# Extension_CN.net
KiCad netlist of a schematic drawn in Altium Designer
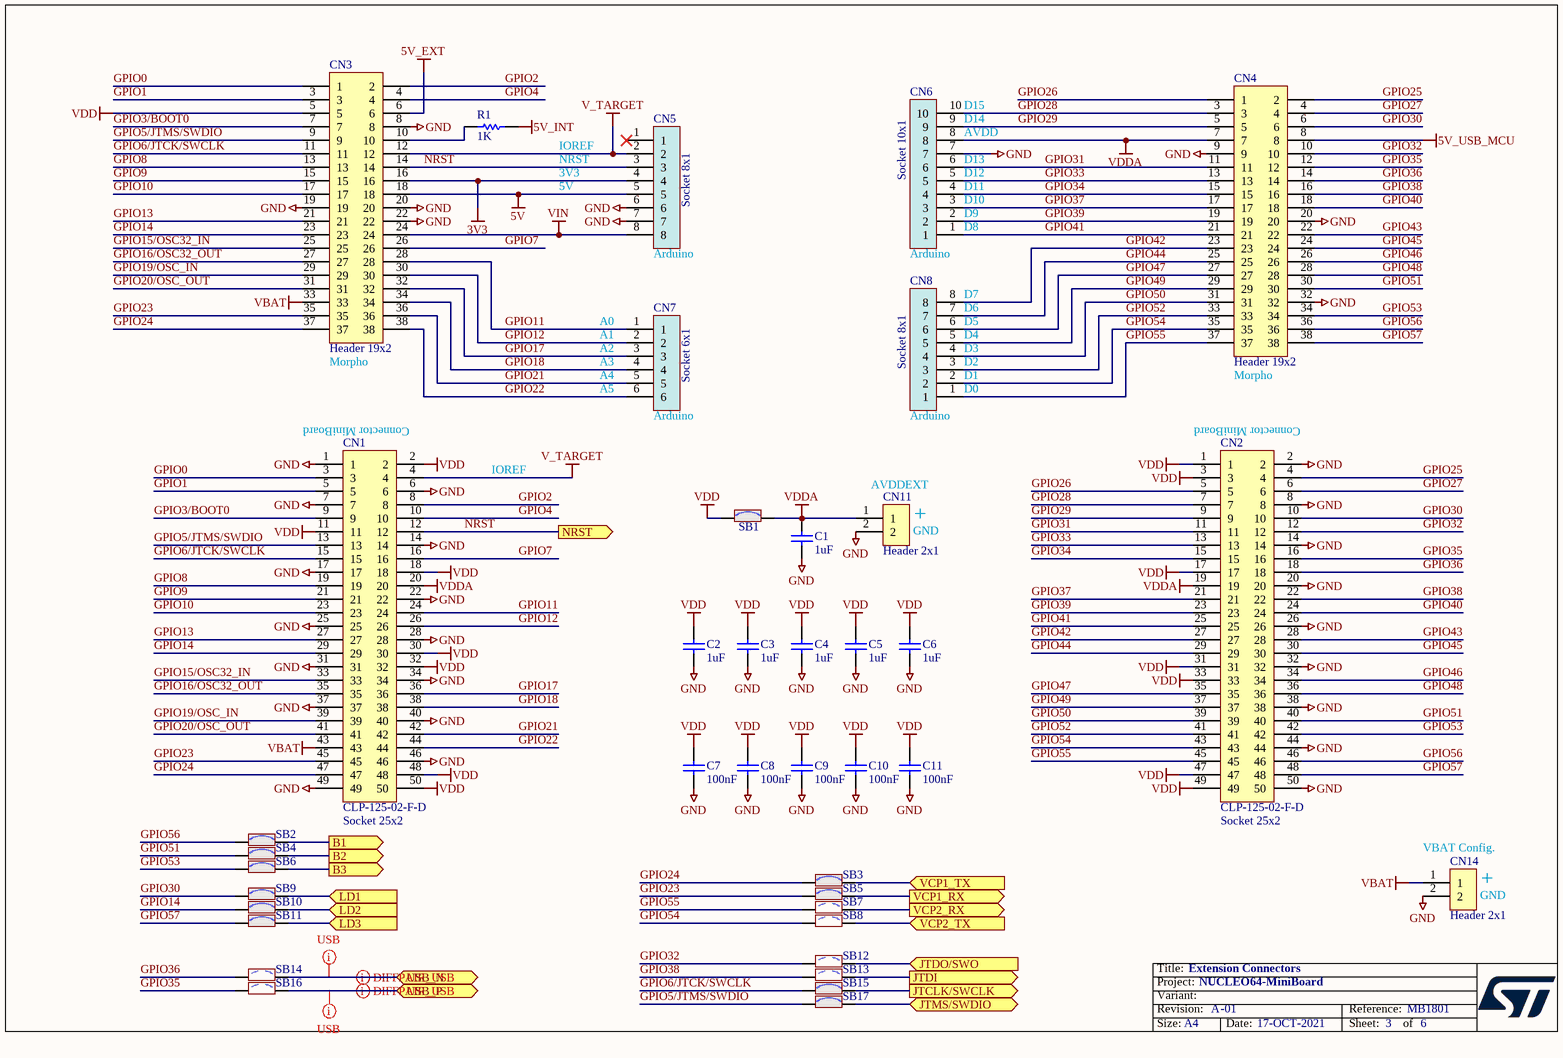
[diagram p0: Extension_CN.SchDoc]

(export (version "E")
  (design (tool "Eeschema 10.0.6"))
  (components
    (comp (ref "C1")
      (value "1uF")
      (footprint "C0805_H0P85")
      (description "Capacitor, MLCC, 1uF, 16V, X5R, +/-10%, 0805, T=0.85mm")
      (fields
        (field (name "INTERNAL_PART_NUMBER") "MCD-01550")
        (field (name "MANUFACTURER_PART_NUMBER") "CC0805KRX5R7BB105")
      )
      (libsource (lib "MCD_PARTS_database") (part "Capacitor"))
    )
    (comp (ref "C2")
      (value "1uF")
      (footprint "C0805_H0P85")
      (description "Capacitor, MLCC, 1uF, 16V, X5R, +/-10%, 0805, T=0.85mm")
      (fields
        (field (name "INTERNAL_PART_NUMBER") "MCD-01550")
        (field (name "MANUFACTURER_PART_NUMBER") "CC0805KRX5R7BB105")
      )
      (libsource (lib "MCD_PARTS_database") (part "Capacitor"))
    )
    (comp (ref "C3")
      (value "1uF")
      (footprint "C0805_H0P85")
      (description "Capacitor, MLCC, 1uF, 16V, X5R, +/-10%, 0805, T=0.85mm")
      (fields
        (field (name "INTERNAL_PART_NUMBER") "MCD-01550")
        (field (name "MANUFACTURER_PART_NUMBER") "CC0805KRX5R7BB105")
      )
      (libsource (lib "MCD_PARTS_database") (part "Capacitor"))
    )
    (comp (ref "C4")
      (value "1uF")
      (footprint "C0805_H0P85")
      (description "Capacitor, MLCC, 1uF, 16V, X5R, +/-10%, 0805, T=0.85mm")
      (fields
        (field (name "INTERNAL_PART_NUMBER") "MCD-01550")
        (field (name "MANUFACTURER_PART_NUMBER") "CC0805KRX5R7BB105")
      )
      (libsource (lib "MCD_PARTS_database") (part "Capacitor"))
    )
    (comp (ref "C5")
      (value "1uF")
      (footprint "C0805_H0P85")
      (description "Capacitor, MLCC, 1uF, 16V, X5R, +/-10%, 0805, T=0.85mm")
      (fields
        (field (name "INTERNAL_PART_NUMBER") "MCD-01550")
        (field (name "MANUFACTURER_PART_NUMBER") "CC0805KRX5R7BB105")
      )
      (libsource (lib "MCD_PARTS_database") (part "Capacitor"))
    )
    (comp (ref "C6")
      (value "1uF")
      (footprint "C0805_H0P85")
      (description "Capacitor, MLCC, 1uF, 16V, X5R, +/-10%, 0805, T=0.85mm")
      (fields
        (field (name "INTERNAL_PART_NUMBER") "MCD-01550")
        (field (name "MANUFACTURER_PART_NUMBER") "CC0805KRX5R7BB105")
      )
      (libsource (lib "MCD_PARTS_database") (part "Capacitor"))
    )
    (comp (ref "C7")
      (value "100nF")
      (footprint "C0402")
      (description "Capacitor, MLCC, 100nF, 25V, X7R, +/-10%, 0402, T=0.5mm")
      (fields (field (name "INTERNAL_PART_NUMBER") "MCD-02355") (field (name "MANUFACTURER") "WALSIN"))
      (libsource (lib "MCD_PARTS_database") (part "Capacitor"))
    )
    (comp (ref "C8")
      (value "100nF")
      (footprint "C0402")
      (description "Capacitor, MLCC, 100nF, 25V, X7R, +/-10%, 0402, T=0.5mm")
      (fields (field (name "INTERNAL_PART_NUMBER") "MCD-02355") (field (name "MANUFACTURER") "WALSIN"))
      (libsource (lib "MCD_PARTS_database") (part "Capacitor"))
    )
    (comp (ref "C9")
      (value "100nF")
      (footprint "C0402")
      (description "Capacitor, MLCC, 100nF, 25V, X7R, +/-10%, 0402, T=0.5mm")
      (fields (field (name "INTERNAL_PART_NUMBER") "MCD-02355") (field (name "MANUFACTURER") "WALSIN"))
      (libsource (lib "MCD_PARTS_database") (part "Capacitor"))
    )
    (comp (ref "C10")
      (value "100nF")
      (footprint "C0402")
      (description "Capacitor, MLCC, 100nF, 25V, X7R, +/-10%, 0402, T=0.5mm")
      (fields (field (name "INTERNAL_PART_NUMBER") "MCD-02355") (field (name "MANUFACTURER") "WALSIN"))
      (libsource (lib "MCD_PARTS_database") (part "Capacitor"))
    )
    (comp (ref "C11")
      (value "100nF")
      (footprint "C0402")
      (description "Capacitor, MLCC, 100nF, 25V, X7R, +/-10%, 0402, T=0.5mm")
      (fields (field (name "INTERNAL_PART_NUMBER") "MCD-02355") (field (name "MANUFACTURER") "WALSIN"))
      (libsource (lib "MCD_PARTS_database") (part "Capacitor"))
    )
    (comp (ref "CN1")
      (value "CLP-125-02-F-D")
      (footprint "CON_SAMTEC_CLP-125-02-F-D")
      (description "Socket, 25x2, 1.27mm, VR, SMD, T=2.29mm")
      (fields
        (field (name "INTERNAL_PART_NUMBER") "MCD-02705")
        (field (name "ALTIUM_VALUE") "Socket 25x2")
        (field (name "MANUFACTURER") "SAMTEC")
      )
      (libsource (lib "MCD_PARTS_database") (part "CLP-125-02-F-D"))
    )
    (comp (ref "CN2")
      (value "CLP-125-02-F-D")
      (footprint "CON_SAMTEC_CLP-125-02-F-D")
      (description "Socket, 25x2, 1.27mm, VR, SMD, T=2.29mm")
      (fields
        (field (name "INTERNAL_PART_NUMBER") "MCD-02705")
        (field (name "ALTIUM_VALUE") "Socket 25x2")
        (field (name "MANUFACTURER") "SAMTEC")
      )
      (libsource (lib "MCD_PARTS_database") (part "CLP-125-02-F-D"))
    )
    (comp (ref "CN3")
      (value "Header 19x2")
      (footprint "CON_SAMTEC_TSW-119-09-X-D")
      (description "Header, 19x2, 2.54mm, VR, TH, T=5.84mm/10.16mm")
      (fields (field (name "INTERNAL_PART_NUMBER") "MCD-00213") (field (name "MANUFACTURER") "SAMTEC"))
      (libsource (lib "MCD_PARTS_database") (part "Header 19x2"))
    )
    (comp (ref "CN4")
      (value "Header 19x2")
      (footprint "CON_SAMTEC_TSW-119-09-X-D")
      (description "Header, 19x2, 2.54mm, VR, TH, T=5.84mm/10.16mm")
      (fields (field (name "INTERNAL_PART_NUMBER") "MCD-00213") (field (name "MANUFACTURER") "SAMTEC"))
      (libsource (lib "MCD_PARTS_database") (part "Header 19x2"))
    )
    (comp (ref "CN5")
      (value "Socket 8x1")
      (footprint "CON_SAMTEC_SSW-108-01-X-S")
      (description "Socket, 8x1, 2.54mm, VR, TH, T=8.51/2.64mm")
      (fields (field (name "INTERNAL_PART_NUMBER") "MCD-01743") (field (name "MANUFACTURER") "SAMTEC"))
      (libsource (lib "") (part "Socket 8x1_1"))
    )
    (comp (ref "CN6")
      (value "Socket 10x1")
      (footprint "CON_SAMTEC_SSW-110-01-X-S")
      (description "Socket, 10x1, 2.54mm, VR, TH, T=8.51/2.64mm")
      (fields (field (name "INTERNAL_PART_NUMBER") "MCD-02080") (field (name "MANUFACTURER") "SAMTEC"))
      (libsource (lib "MCD_PARTS_database") (part "Socket 10x1"))
    )
    (comp (ref "CN7")
      (value "Socket 6x1")
      (footprint "CON_SAMTEC_SSW-106-01-X-S")
      (description "Socket, 6x1, 2.54mm, VR, TH, T=8.51/2.64mm")
      (fields (field (name "INTERNAL_PART_NUMBER") "MCD-02079") (field (name "MANUFACTURER") "SAMTEC"))
      (libsource (lib "MCD_PARTS_database") (part "Socket 6x1"))
    )
    (comp (ref "CN8")
      (value "Socket 8x1")
      (footprint "CON_SAMTEC_SSW-108-01-X-S")
      (description "Socket, 8x1, 2.54mm, VR, TH, T=8.51/2.64mm")
      (fields (field (name "INTERNAL_PART_NUMBER") "MCD-01743") (field (name "MANUFACTURER") "SAMTEC"))
      (libsource (lib "MCD_PARTS_database") (part "Socket 8x1"))
    )
    (comp (ref "CN11")
      (value "Header 2x1")
      (footprint "CON_SAMTEC_TSW-102-07-G-S")
      (description "Header, 2x1, 2.54mm, VR, TH, T=5.84mm/2.54mm")
      (fields (field (name "INTERNAL_PART_NUMBER") "MCD-00032") (field (name "MANUFACTURER") "SAMTEC"))
      (libsource (lib "MCD_PARTS_database") (part "Header 2x1"))
    )
    (comp (ref "CN14")
      (value "Header 2x1")
      (footprint "CON_SAMTEC_TSW-102-07-G-S")
      (description "Header, 2x1, 2.54mm, VR, TH, T=5.84mm/2.54mm")
      (fields (field (name "INTERNAL_PART_NUMBER") "MCD-00032") (field (name "MANUFACTURER") "SAMTEC"))
      (libsource (lib "MCD_PARTS_database") (part "Header 2x1"))
    )
    (comp (ref "R1")
      (value "1K")
      (footprint "R0402")
      (description "Resistor, 1K, 0402, +/-1%,1/16W")
      (fields (field (name "INTERNAL_PART_NUMBER") "MCD-00061") (field (name "MANUFACTURER") "YAGEO"))
      (libsource (lib "MCD_PARTS_database") (part "Resistor"))
    )
    (comp (ref "SB1")
      (value "SB_ON")
      (footprint "SOLDER-BRIDGE_R0402-0R")
      (description "Solder Bridge 0402 ON")
      (fields (field (name "INTERNAL_PART_NUMBER") "MCD-01618") (field (name "MANUFACTURER") "YAGEO"))
      (libsource (lib "MCD_PARTS_database") (part "SB_ON"))
    )
    (comp (ref "SB2")
      (value "SB_ON")
      (footprint "SOLDER-BRIDGE_R0402-0R")
      (description "Solder Bridge 0402 ON")
      (fields (field (name "INTERNAL_PART_NUMBER") "MCD-01618") (field (name "MANUFACTURER") "YAGEO"))
      (libsource (lib "MCD_PARTS_database") (part "SB_ON"))
    )
    (comp (ref "SB3")
      (value "SB_ON")
      (footprint "SOLDER-BRIDGE_R0402-0R")
      (description "Solder Bridge 0402 ON")
      (fields (field (name "INTERNAL_PART_NUMBER") "MCD-01618") (field (name "MANUFACTURER") "YAGEO"))
      (libsource (lib "MCD_PARTS_database") (part "SB_ON"))
    )
    (comp (ref "SB4")
      (value "SB_ON")
      (footprint "SOLDER-BRIDGE_R0402-0R")
      (description "Solder Bridge 0402 ON")
      (fields (field (name "INTERNAL_PART_NUMBER") "MCD-01618") (field (name "MANUFACTURER") "YAGEO"))
      (libsource (lib "MCD_PARTS_database") (part "SB_ON"))
    )
    (comp (ref "SB5")
      (value "SB_ON")
      (footprint "SOLDER-BRIDGE_R0402-0R")
      (description "Solder Bridge 0402 ON")
      (fields (field (name "INTERNAL_PART_NUMBER") "MCD-01618") (field (name "MANUFACTURER") "YAGEO"))
      (libsource (lib "MCD_PARTS_database") (part "SB_ON"))
    )
    (comp (ref "SB6")
      (value "SB_ON")
      (footprint "SOLDER-BRIDGE_R0402-0R")
      (description "Solder Bridge 0402 ON")
      (fields (field (name "INTERNAL_PART_NUMBER") "MCD-01618") (field (name "MANUFACTURER") "YAGEO"))
      (libsource (lib "MCD_PARTS_database") (part "SB_ON"))
    )
    (comp (ref "SB7")
      (value "SB_OFF")
      (footprint "SOLDER-BRIDGE_R0402-0R")
      (description "Solder Bridge 0402 OFF")
      (fields (field (name "INTERNAL_PART_NUMBER") "MCD-02162") (field (name "MANUFACTURER") "YAGEO"))
      (libsource (lib "MCD_PARTS_database") (part "SB_OFF"))
    )
    (comp (ref "SB8")
      (value "SB_OFF")
      (footprint "SOLDER-BRIDGE_R0402-0R")
      (description "Solder Bridge 0402 OFF")
      (fields (field (name "INTERNAL_PART_NUMBER") "MCD-02162") (field (name "MANUFACTURER") "YAGEO"))
      (libsource (lib "MCD_PARTS_database") (part "SB_OFF"))
    )
    (comp (ref "SB9")
      (value "SB_ON")
      (footprint "SOLDER-BRIDGE_R0402-0R")
      (description "Solder Bridge 0402 ON")
      (fields (field (name "INTERNAL_PART_NUMBER") "MCD-01618") (field (name "MANUFACTURER") "YAGEO"))
      (libsource (lib "MCD_PARTS_database") (part "SB_ON"))
    )
    (comp (ref "SB10")
      (value "SB_ON")
      (footprint "SOLDER-BRIDGE_R0402-0R")
      (description "Solder Bridge 0402 ON")
      (fields (field (name "INTERNAL_PART_NUMBER") "MCD-01618") (field (name "MANUFACTURER") "YAGEO"))
      (libsource (lib "MCD_PARTS_database") (part "SB_ON"))
    )
    (comp (ref "SB11")
      (value "SB_ON")
      (footprint "SOLDER-BRIDGE_R0402-0R")
      (description "Solder Bridge 0402 ON")
      (fields (field (name "INTERNAL_PART_NUMBER") "MCD-01618") (field (name "MANUFACTURER") "YAGEO"))
      (libsource (lib "MCD_PARTS_database") (part "SB_ON"))
    )
    (comp (ref "SB12")
      (value "SB_OFF")
      (footprint "SOLDER-BRIDGE_R0402-0R")
      (description "Solder Bridge 0402 OFF")
      (fields (field (name "INTERNAL_PART_NUMBER") "MCD-02162") (field (name "MANUFACTURER") "YAGEO"))
      (libsource (lib "MCD_PARTS_database") (part "SB_OFF"))
    )
    (comp (ref "SB13")
      (value "SB_OFF")
      (footprint "SOLDER-BRIDGE_R0402-0R")
      (description "Solder Bridge 0402 OFF")
      (fields (field (name "INTERNAL_PART_NUMBER") "MCD-02162") (field (name "MANUFACTURER") "YAGEO"))
      (libsource (lib "MCD_PARTS_database") (part "SB_OFF"))
    )
    (comp (ref "SB14")
      (value "SB_OFF")
      (footprint "SOLDER-BRIDGE_R0402-0R")
      (description "Solder Bridge 0402 OFF")
      (fields (field (name "INTERNAL_PART_NUMBER") "MCD-02162") (field (name "MANUFACTURER") "YAGEO"))
      (libsource (lib "MCD_PARTS_database") (part "SB_OFF"))
    )
    (comp (ref "SB15")
      (value "SB_ON")
      (footprint "SOLDER-BRIDGE_R0402-0R")
      (description "Solder Bridge 0402 ON")
      (fields (field (name "INTERNAL_PART_NUMBER") "MCD-01618") (field (name "MANUFACTURER") "YAGEO"))
      (libsource (lib "MCD_PARTS_database") (part "SB_ON"))
    )
    (comp (ref "SB16")
      (value "SB_OFF")
      (footprint "SOLDER-BRIDGE_R0402-0R")
      (description "Solder Bridge 0402 OFF")
      (fields (field (name "INTERNAL_PART_NUMBER") "MCD-02162") (field (name "MANUFACTURER") "YAGEO"))
      (libsource (lib "MCD_PARTS_database") (part "SB_OFF"))
    )
    (comp (ref "SB17")
      (value "SB_ON")
      (footprint "SOLDER-BRIDGE_R0402-0R")
      (description "Solder Bridge 0402 ON")
      (fields (field (name "INTERNAL_PART_NUMBER") "MCD-01618") (field (name "MANUFACTURER") "YAGEO"))
      (libsource (lib "MCD_PARTS_database") (part "SB_ON"))
    )
  )
  (nets
    (net (code "1") (name "/B1") (class "Default")
      (node (ref "SB2") (pin "2") (pinfunction "2_2") (pintype "passive"))
    )
    (net (code "2") (name "/B2") (class "Default")
      (node (ref "SB4") (pin "2") (pinfunction "2_2") (pintype "passive"))
    )
    (net (code "3") (name "/B3") (class "Default")
      (node (ref "SB6") (pin "2") (pinfunction "2_2") (pintype "passive"))
    )
    (net (code "4") (name "/GPIO0") (class "Default")
      (node (ref "CN1") (pin "3") (pinfunction "3_3") (pintype "passive"))
      (node (ref "CN3") (pin "1") (pinfunction "1_1") (pintype "passive"))
    )
    (net (code "5") (name "/GPIO1") (class "Default")
      (node (ref "CN1") (pin "5") (pinfunction "5_5") (pintype "passive"))
      (node (ref "CN3") (pin "3") (pinfunction "3_3") (pintype "passive"))
    )
    (net (code "6") (name "/GPIO2") (class "Default")
      (node (ref "CN1") (pin "8") (pinfunction "8_8") (pintype "passive"))
      (node (ref "CN3") (pin "2") (pinfunction "2_2") (pintype "passive"))
    )
    (net (code "7") (name "/GPIO3{slash}BOOT0") (class "Default")
      (node (ref "CN1") (pin "9") (pinfunction "9_9") (pintype "passive"))
      (node (ref "CN3") (pin "7") (pinfunction "7_7") (pintype "passive"))
    )
    (net (code "8") (name "/GPIO4") (class "Default")
      (node (ref "CN1") (pin "10") (pinfunction "10_10") (pintype "passive"))
      (node (ref "CN3") (pin "4") (pinfunction "4_4") (pintype "passive"))
    )
    (net (code "9") (name "/GPIO5{slash}JTMS{slash}SWDIO") (class "Default")
      (node (ref "CN1") (pin "13") (pinfunction "13_13") (pintype "passive"))
      (node (ref "CN3") (pin "9") (pinfunction "9_9") (pintype "passive"))
      (node (ref "SB17") (pin "1") (pinfunction "1_1") (pintype "passive"))
    )
    (net (code "10") (name "/GPIO6{slash}JTCK{slash}SWCLK") (class "Default")
      (node (ref "CN1") (pin "15") (pinfunction "15_15") (pintype "passive"))
      (node (ref "CN3") (pin "11") (pinfunction "11_11") (pintype "passive"))
      (node (ref "SB15") (pin "1") (pinfunction "1_1") (pintype "passive"))
    )
    (net (code "11") (name "/GPIO7") (class "Default")
      (node (ref "CN1") (pin "16") (pinfunction "16_16") (pintype "passive"))
      (node (ref "CN3") (pin "26") (pinfunction "26_26") (pintype "passive"))
    )
    (net (code "12") (name "/GPIO8") (class "Default")
      (node (ref "CN1") (pin "19") (pinfunction "19_19") (pintype "passive"))
      (node (ref "CN3") (pin "13") (pinfunction "13_13") (pintype "passive"))
    )
    (net (code "13") (name "/GPIO9") (class "Default")
      (node (ref "CN1") (pin "21") (pinfunction "21_21") (pintype "passive"))
      (node (ref "CN3") (pin "15") (pinfunction "15_15") (pintype "passive"))
    )
    (net (code "14") (name "/GPIO10") (class "Default")
      (node (ref "CN1") (pin "23") (pinfunction "23_23") (pintype "passive"))
      (node (ref "CN3") (pin "17") (pinfunction "17_17") (pintype "passive"))
    )
    (net (code "15") (name "/GPIO11") (class "Default")
      (node (ref "CN1") (pin "24") (pinfunction "24_24") (pintype "passive"))
      (node (ref "CN3") (pin "28") (pinfunction "28_28") (pintype "passive"))
      (node (ref "CN7") (pin "1") (pinfunction "1_1") (pintype "passive"))
    )
    (net (code "16") (name "/GPIO12") (class "Default")
      (node (ref "CN1") (pin "26") (pinfunction "26_26") (pintype "passive"))
      (node (ref "CN3") (pin "30") (pinfunction "30_30") (pintype "passive"))
      (node (ref "CN7") (pin "2") (pinfunction "2_2") (pintype "passive"))
    )
    (net (code "17") (name "/GPIO13") (class "Default")
      (node (ref "CN1") (pin "27") (pinfunction "27_27") (pintype "passive"))
      (node (ref "CN3") (pin "21") (pinfunction "21_21") (pintype "passive"))
    )
    (net (code "18") (name "/GPIO14") (class "Default")
      (node (ref "CN1") (pin "29") (pinfunction "29_29") (pintype "passive"))
      (node (ref "CN3") (pin "23") (pinfunction "23_23") (pintype "passive"))
      (node (ref "SB10") (pin "1") (pinfunction "1_1") (pintype "passive"))
    )
    (net (code "19") (name "/GPIO15{slash}OSC32_IN") (class "Default")
      (node (ref "CN1") (pin "33") (pinfunction "33_33") (pintype "passive"))
      (node (ref "CN3") (pin "25") (pinfunction "25_25") (pintype "passive"))
    )
    (net (code "20") (name "/GPIO16{slash}OSC32_OUT") (class "Default")
      (node (ref "CN1") (pin "35") (pinfunction "35_35") (pintype "passive"))
      (node (ref "CN3") (pin "27") (pinfunction "27_27") (pintype "passive"))
    )
    (net (code "21") (name "/GPIO17") (class "Default")
      (node (ref "CN1") (pin "36") (pinfunction "36_36") (pintype "passive"))
      (node (ref "CN3") (pin "32") (pinfunction "32_32") (pintype "passive"))
      (node (ref "CN7") (pin "3") (pinfunction "3_3") (pintype "passive"))
    )
    (net (code "22") (name "/GPIO18") (class "Default")
      (node (ref "CN1") (pin "38") (pinfunction "38_38") (pintype "passive"))
      (node (ref "CN3") (pin "34") (pinfunction "34_34") (pintype "passive"))
      (node (ref "CN7") (pin "4") (pinfunction "4_4") (pintype "passive"))
    )
    (net (code "23") (name "/GPIO19{slash}OSC_IN") (class "Default")
      (node (ref "CN1") (pin "39") (pinfunction "39_39") (pintype "passive"))
      (node (ref "CN3") (pin "29") (pinfunction "29_29") (pintype "passive"))
    )
    (net (code "24") (name "/GPIO20{slash}OSC_OUT") (class "Default")
      (node (ref "CN1") (pin "41") (pinfunction "41_41") (pintype "passive"))
      (node (ref "CN3") (pin "31") (pinfunction "31_31") (pintype "passive"))
    )
    (net (code "25") (name "/GPIO21") (class "Default")
      (node (ref "CN1") (pin "42") (pinfunction "42_42") (pintype "passive"))
      (node (ref "CN3") (pin "36") (pinfunction "36_36") (pintype "passive"))
      (node (ref "CN7") (pin "5") (pinfunction "5_5") (pintype "passive"))
    )
    (net (code "26") (name "/GPIO22") (class "Default")
      (node (ref "CN1") (pin "44") (pinfunction "44_44") (pintype "passive"))
      (node (ref "CN3") (pin "38") (pinfunction "38_38") (pintype "passive"))
      (node (ref "CN7") (pin "6") (pinfunction "6_6") (pintype "passive"))
    )
    (net (code "27") (name "/GPIO23") (class "Default")
      (node (ref "CN1") (pin "45") (pinfunction "45_45") (pintype "passive"))
      (node (ref "CN3") (pin "35") (pinfunction "35_35") (pintype "passive"))
      (node (ref "SB5") (pin "1") (pinfunction "1_1") (pintype "passive"))
    )
    (net (code "28") (name "/GPIO24") (class "Default")
      (node (ref "CN1") (pin "47") (pinfunction "47_47") (pintype "passive"))
      (node (ref "CN3") (pin "37") (pinfunction "37_37") (pintype "passive"))
      (node (ref "SB3") (pin "1") (pinfunction "1_1") (pintype "passive"))
    )
    (net (code "29") (name "/GPIO25") (class "Default")
      (node (ref "CN2") (pin "4") (pinfunction "4_4") (pintype "passive"))
      (node (ref "CN4") (pin "2") (pinfunction "2_2") (pintype "passive"))
    )
    (net (code "30") (name "/GPIO26") (class "Default")
      (node (ref "CN2") (pin "5") (pinfunction "5_5") (pintype "passive"))
      (node (ref "CN4") (pin "1") (pinfunction "1_1") (pintype "passive"))
    )
    (net (code "31") (name "/GPIO27") (class "Default")
      (node (ref "CN2") (pin "6") (pinfunction "6_6") (pintype "passive"))
      (node (ref "CN4") (pin "4") (pinfunction "4_4") (pintype "passive"))
    )
    (net (code "32") (name "/GPIO28") (class "Default")
      (node (ref "CN2") (pin "7") (pinfunction "7_7") (pintype "passive"))
      (node (ref "CN4") (pin "3") (pinfunction "3_3") (pintype "passive"))
      (node (ref "CN6") (pin "10") (pinfunction "10_10") (pintype "passive"))
    )
    (net (code "33") (name "/GPIO29") (class "Default")
      (node (ref "CN2") (pin "9") (pinfunction "9_9") (pintype "passive"))
      (node (ref "CN4") (pin "5") (pinfunction "5_5") (pintype "passive"))
      (node (ref "CN6") (pin "9") (pinfunction "9_9") (pintype "passive"))
    )
    (net (code "34") (name "/GPIO30") (class "Default")
      (node (ref "CN2") (pin "10") (pinfunction "10_10") (pintype "passive"))
      (node (ref "CN4") (pin "6") (pinfunction "6_6") (pintype "passive"))
      (node (ref "SB9") (pin "1") (pinfunction "1_1") (pintype "passive"))
    )
    (net (code "35") (name "/GPIO31") (class "Default")
      (node (ref "CN2") (pin "11") (pinfunction "11_11") (pintype "passive"))
      (node (ref "CN4") (pin "11") (pinfunction "11_11") (pintype "passive"))
      (node (ref "CN6") (pin "6") (pinfunction "6_6") (pintype "passive"))
    )
    (net (code "36") (name "/GPIO32") (class "Default")
      (node (ref "CN2") (pin "12") (pinfunction "12_12") (pintype "passive"))
      (node (ref "CN4") (pin "10") (pinfunction "10_10") (pintype "passive"))
      (node (ref "SB12") (pin "1") (pinfunction "1_1") (pintype "passive"))
    )
    (net (code "37") (name "/GPIO33") (class "Default")
      (node (ref "CN2") (pin "13") (pinfunction "13_13") (pintype "passive"))
      (node (ref "CN4") (pin "13") (pinfunction "13_13") (pintype "passive"))
      (node (ref "CN6") (pin "5") (pinfunction "5_5") (pintype "passive"))
    )
    (net (code "38") (name "/GPIO34") (class "Default")
      (node (ref "CN2") (pin "15") (pinfunction "15_15") (pintype "passive"))
      (node (ref "CN4") (pin "15") (pinfunction "15_15") (pintype "passive"))
      (node (ref "CN6") (pin "4") (pinfunction "4_4") (pintype "passive"))
    )
    (net (code "39") (name "/GPIO35") (class "Default")
      (node (ref "CN2") (pin "16") (pinfunction "16_16") (pintype "passive"))
      (node (ref "CN4") (pin "12") (pinfunction "12_12") (pintype "passive"))
      (node (ref "SB16") (pin "1") (pinfunction "1_1") (pintype "passive"))
    )
    (net (code "40") (name "/GPIO36") (class "Default")
      (node (ref "CN2") (pin "18") (pinfunction "18_18") (pintype "passive"))
      (node (ref "CN4") (pin "14") (pinfunction "14_14") (pintype "passive"))
      (node (ref "SB14") (pin "1") (pinfunction "1_1") (pintype "passive"))
    )
    (net (code "41") (name "/GPIO37") (class "Default")
      (node (ref "CN2") (pin "21") (pinfunction "21_21") (pintype "passive"))
      (node (ref "CN4") (pin "17") (pinfunction "17_17") (pintype "passive"))
      (node (ref "CN6") (pin "3") (pinfunction "3_3") (pintype "passive"))
    )
    (net (code "42") (name "/GPIO38") (class "Default")
      (node (ref "CN2") (pin "22") (pinfunction "22_22") (pintype "passive"))
      (node (ref "CN4") (pin "16") (pinfunction "16_16") (pintype "passive"))
      (node (ref "SB13") (pin "1") (pinfunction "1_1") (pintype "passive"))
    )
    (net (code "43") (name "/GPIO39") (class "Default")
      (node (ref "CN2") (pin "23") (pinfunction "23_23") (pintype "passive"))
      (node (ref "CN4") (pin "19") (pinfunction "19_19") (pintype "passive"))
      (node (ref "CN6") (pin "2") (pinfunction "2_2") (pintype "passive"))
    )
    (net (code "44") (name "/GPIO40") (class "Default")
      (node (ref "CN2") (pin "24") (pinfunction "24_24") (pintype "passive"))
      (node (ref "CN4") (pin "18") (pinfunction "18_18") (pintype "passive"))
    )
    (net (code "45") (name "/GPIO41") (class "Default")
      (node (ref "CN2") (pin "25") (pinfunction "25_25") (pintype "passive"))
      (node (ref "CN4") (pin "21") (pinfunction "21_21") (pintype "passive"))
      (node (ref "CN6") (pin "1") (pinfunction "1_1") (pintype "passive"))
    )
    (net (code "46") (name "/GPIO42") (class "Default")
      (node (ref "CN2") (pin "27") (pinfunction "27_27") (pintype "passive"))
      (node (ref "CN4") (pin "23") (pinfunction "23_23") (pintype "passive"))
      (node (ref "CN8") (pin "8") (pinfunction "8_8") (pintype "passive"))
    )
    (net (code "47") (name "/GPIO43") (class "Default")
      (node (ref "CN2") (pin "28") (pinfunction "28_28") (pintype "passive"))
      (node (ref "CN4") (pin "22") (pinfunction "22_22") (pintype "passive"))
    )
    (net (code "48") (name "/GPIO44") (class "Default")
      (node (ref "CN2") (pin "29") (pinfunction "29_29") (pintype "passive"))
      (node (ref "CN4") (pin "25") (pinfunction "25_25") (pintype "passive"))
      (node (ref "CN8") (pin "7") (pinfunction "7_7") (pintype "passive"))
    )
    (net (code "49") (name "/GPIO45") (class "Default")
      (node (ref "CN2") (pin "30") (pinfunction "30_30") (pintype "passive"))
      (node (ref "CN4") (pin "24") (pinfunction "24_24") (pintype "passive"))
    )
    (net (code "50") (name "/GPIO46") (class "Default")
      (node (ref "CN2") (pin "34") (pinfunction "34_34") (pintype "passive"))
      (node (ref "CN4") (pin "26") (pinfunction "26_26") (pintype "passive"))
    )
    (net (code "51") (name "/GPIO47") (class "Default")
      (node (ref "CN2") (pin "35") (pinfunction "35_35") (pintype "passive"))
      (node (ref "CN4") (pin "27") (pinfunction "27_27") (pintype "passive"))
      (node (ref "CN8") (pin "6") (pinfunction "6_6") (pintype "passive"))
    )
    (net (code "52") (name "/GPIO48") (class "Default")
      (node (ref "CN2") (pin "36") (pinfunction "36_36") (pintype "passive"))
      (node (ref "CN4") (pin "28") (pinfunction "28_28") (pintype "passive"))
    )
    (net (code "53") (name "/GPIO49") (class "Default")
      (node (ref "CN2") (pin "37") (pinfunction "37_37") (pintype "passive"))
      (node (ref "CN4") (pin "29") (pinfunction "29_29") (pintype "passive"))
      (node (ref "CN8") (pin "5") (pinfunction "5_5") (pintype "passive"))
    )
    (net (code "54") (name "/GPIO50") (class "Default")
      (node (ref "CN2") (pin "39") (pinfunction "39_39") (pintype "passive"))
      (node (ref "CN4") (pin "31") (pinfunction "31_31") (pintype "passive"))
      (node (ref "CN8") (pin "4") (pinfunction "4_4") (pintype "passive"))
    )
    (net (code "55") (name "/GPIO51") (class "Default")
      (node (ref "CN2") (pin "40") (pinfunction "40_40") (pintype "passive"))
      (node (ref "CN4") (pin "30") (pinfunction "30_30") (pintype "passive"))
      (node (ref "SB4") (pin "1") (pinfunction "1_1") (pintype "passive"))
    )
    (net (code "56") (name "/GPIO52") (class "Default")
      (node (ref "CN2") (pin "41") (pinfunction "41_41") (pintype "passive"))
      (node (ref "CN4") (pin "33") (pinfunction "33_33") (pintype "passive"))
      (node (ref "CN8") (pin "3") (pinfunction "3_3") (pintype "passive"))
    )
    (net (code "57") (name "/GPIO53") (class "Default")
      (node (ref "CN2") (pin "42") (pinfunction "42_42") (pintype "passive"))
      (node (ref "CN4") (pin "34") (pinfunction "34_34") (pintype "passive"))
      (node (ref "SB6") (pin "1") (pinfunction "1_1") (pintype "passive"))
    )
    (net (code "58") (name "/GPIO54") (class "Default")
      (node (ref "CN2") (pin "43") (pinfunction "43_43") (pintype "passive"))
      (node (ref "CN4") (pin "35") (pinfunction "35_35") (pintype "passive"))
      (node (ref "CN8") (pin "2") (pinfunction "2_2") (pintype "passive"))
      (node (ref "SB8") (pin "1") (pinfunction "1_1") (pintype "passive"))
    )
    (net (code "59") (name "/GPIO55") (class "Default")
      (node (ref "CN2") (pin "45") (pinfunction "45_45") (pintype "passive"))
      (node (ref "CN4") (pin "37") (pinfunction "37_37") (pintype "passive"))
      (node (ref "CN8") (pin "1") (pinfunction "1_1") (pintype "passive"))
      (node (ref "SB7") (pin "1") (pinfunction "1_1") (pintype "passive"))
    )
    (net (code "60") (name "/GPIO56") (class "Default")
      (node (ref "CN2") (pin "46") (pinfunction "46_46") (pintype "passive"))
      (node (ref "CN4") (pin "36") (pinfunction "36_36") (pintype "passive"))
      (node (ref "SB2") (pin "1") (pinfunction "1_1") (pintype "passive"))
    )
    (net (code "61") (name "/GPIO57") (class "Default")
      (node (ref "CN2") (pin "48") (pinfunction "48_48") (pintype "passive"))
      (node (ref "CN4") (pin "38") (pinfunction "38_38") (pintype "passive"))
      (node (ref "SB11") (pin "1") (pinfunction "1_1") (pintype "passive"))
    )
    (net (code "62") (name "/JTCLK{slash}SWCLK") (class "Default")
      (node (ref "SB15") (pin "2") (pinfunction "2_2") (pintype "passive"))
    )
    (net (code "63") (name "/JTDI") (class "Default")
      (node (ref "SB13") (pin "2") (pinfunction "2_2") (pintype "passive"))
    )
    (net (code "64") (name "/JTDO{slash}SWO") (class "Default")
      (node (ref "SB12") (pin "2") (pinfunction "2_2") (pintype "passive"))
    )
    (net (code "65") (name "/JTMS{slash}SWDIO") (class "Default")
      (node (ref "SB17") (pin "2") (pinfunction "2_2") (pintype "passive"))
    )
    (net (code "66") (name "/LD1") (class "Default")
      (node (ref "SB9") (pin "2") (pinfunction "2_2") (pintype "passive"))
    )
    (net (code "67") (name "/LD2") (class "Default")
      (node (ref "SB10") (pin "2") (pinfunction "2_2") (pintype "passive"))
    )
    (net (code "68") (name "/LD3") (class "Default")
      (node (ref "SB11") (pin "2") (pinfunction "2_2") (pintype "passive"))
    )
    (net (code "69") (name "/NRST") (class "Default")
      (node (ref "CN1") (pin "12") (pinfunction "12_12") (pintype "passive"))
      (node (ref "CN3") (pin "14") (pinfunction "14_14") (pintype "passive"))
      (node (ref "CN5") (pin "3") (pinfunction "3_3") (pintype "passive"))
    )
    (net (code "70") (name "/USB_N") (class "Default")
      (node (ref "SB14") (pin "2") (pinfunction "2_2") (pintype "passive"))
    )
    (net (code "71") (name "/USB_P") (class "Default")
      (node (ref "SB16") (pin "2") (pinfunction "2_2") (pintype "passive"))
    )
    (net (code "72") (name "/VCP1_RX") (class "Default")
      (node (ref "SB5") (pin "2") (pinfunction "2_2") (pintype "passive"))
    )
    (net (code "73") (name "/VCP1_TX") (class "Default")
      (node (ref "SB3") (pin "2") (pinfunction "2_2") (pintype "passive"))
    )
    (net (code "74") (name "/VCP2_RX") (class "Default")
      (node (ref "SB7") (pin "2") (pinfunction "2_2") (pintype "passive"))
    )
    (net (code "75") (name "/VCP2_TX") (class "Default")
      (node (ref "SB8") (pin "2") (pinfunction "2_2") (pintype "passive"))
    )
    (net (code "76") (name "3V3") (class "Default")
      (node (ref "CN3") (pin "16") (pinfunction "16_16") (pintype "passive"))
      (node (ref "CN5") (pin "4") (pinfunction "4_4") (pintype "passive"))
    )
    (net (code "77") (name "5V") (class "Default")
      (node (ref "CN3") (pin "18") (pinfunction "18_18") (pintype "passive"))
      (node (ref "CN5") (pin "5") (pinfunction "5_5") (pintype "passive"))
    )
    (net (code "78") (name "5V_EXT") (class "Default")
      (node (ref "CN3") (pin "6") (pinfunction "6_6") (pintype "passive"))
    )
    (net (code "79") (name "5V_INT") (class "Default")
      (node (ref "R1") (pin "2") (pinfunction "2_2") (pintype "passive"))
    )
    (net (code "80") (name "5V_USB_MCU") (class "Default")
      (node (ref "CN4") (pin "8") (pinfunction "8_8") (pintype "passive"))
    )
    (net (code "81") (name "GND") (class "Default")
      (node (ref "C1") (pin "1") (pinfunction "1_1") (pintype "passive"))
      (node (ref "C10") (pin "1") (pinfunction "1_1") (pintype "passive"))
      (node (ref "C11") (pin "1") (pinfunction "1_1") (pintype "passive"))
      (node (ref "C2") (pin "1") (pinfunction "1_1") (pintype "passive"))
      (node (ref "C3") (pin "1") (pinfunction "1_1") (pintype "passive"))
      (node (ref "C4") (pin "1") (pinfunction "1_1") (pintype "passive"))
      (node (ref "C5") (pin "1") (pinfunction "1_1") (pintype "passive"))
      (node (ref "C6") (pin "1") (pinfunction "1_1") (pintype "passive"))
      (node (ref "C7") (pin "1") (pinfunction "1_1") (pintype "passive"))
      (node (ref "C8") (pin "1") (pinfunction "1_1") (pintype "passive"))
      (node (ref "C9") (pin "1") (pinfunction "1_1") (pintype "passive"))
      (node (ref "CN1") (pin "1") (pinfunction "1_1") (pintype "passive"))
      (node (ref "CN1") (pin "14") (pinfunction "14_14") (pintype "passive"))
      (node (ref "CN1") (pin "17") (pinfunction "17_17") (pintype "passive"))
      (node (ref "CN1") (pin "22") (pinfunction "22_22") (pintype "passive"))
      (node (ref "CN1") (pin "25") (pinfunction "25_25") (pintype "passive"))
      (node (ref "CN1") (pin "28") (pinfunction "28_28") (pintype "passive"))
      (node (ref "CN1") (pin "31") (pinfunction "31_31") (pintype "passive"))
      (node (ref "CN1") (pin "34") (pinfunction "34_34") (pintype "passive"))
      (node (ref "CN1") (pin "37") (pinfunction "37_37") (pintype "passive"))
      (node (ref "CN1") (pin "40") (pinfunction "40_40") (pintype "passive"))
      (node (ref "CN1") (pin "46") (pinfunction "46_46") (pintype "passive"))
      (node (ref "CN1") (pin "49") (pinfunction "49_49") (pintype "passive"))
      (node (ref "CN1") (pin "6") (pinfunction "6_6") (pintype "passive"))
      (node (ref "CN1") (pin "7") (pinfunction "7_7") (pintype "passive"))
      (node (ref "CN11") (pin "2") (pinfunction "2_2") (pintype "passive"))
      (node (ref "CN14") (pin "2") (pinfunction "2_2") (pintype "passive"))
      (node (ref "CN2") (pin "14") (pinfunction "14_14") (pintype "passive"))
      (node (ref "CN2") (pin "2") (pinfunction "2_2") (pintype "passive"))
      (node (ref "CN2") (pin "20") (pinfunction "20_20") (pintype "passive"))
      (node (ref "CN2") (pin "26") (pinfunction "26_26") (pintype "passive"))
      (node (ref "CN2") (pin "32") (pinfunction "32_32") (pintype "passive"))
      (node (ref "CN2") (pin "38") (pinfunction "38_38") (pintype "passive"))
      (node (ref "CN2") (pin "44") (pinfunction "44_44") (pintype "passive"))
      (node (ref "CN2") (pin "50") (pinfunction "50_50") (pintype "passive"))
      (node (ref "CN2") (pin "8") (pinfunction "8_8") (pintype "passive"))
      (node (ref "CN3") (pin "19") (pinfunction "19_19") (pintype "passive"))
      (node (ref "CN3") (pin "20") (pinfunction "20_20") (pintype "passive"))
      (node (ref "CN3") (pin "22") (pinfunction "22_22") (pintype "passive"))
      (node (ref "CN3") (pin "8") (pinfunction "8_8") (pintype "passive"))
      (node (ref "CN4") (pin "20") (pinfunction "20_20") (pintype "passive"))
      (node (ref "CN4") (pin "32") (pinfunction "32_32") (pintype "passive"))
      (node (ref "CN4") (pin "9") (pinfunction "9_9") (pintype "passive"))
      (node (ref "CN5") (pin "6") (pinfunction "6_6") (pintype "passive"))
      (node (ref "CN5") (pin "7") (pinfunction "7_7") (pintype "passive"))
      (node (ref "CN6") (pin "7") (pinfunction "7_7") (pintype "passive"))
    )
    (net (code "82") (name "Net-(CN3-Pad10)") (class "Default")
      (node (ref "CN3") (pin "10") (pinfunction "10_10") (pintype "passive"))
      (node (ref "R1") (pin "1") (pinfunction "1_1") (pintype "passive"))
    )
    (net (code "83") (name "VBAT") (class "Default")
      (node (ref "CN1") (pin "43") (pinfunction "43_43") (pintype "passive"))
      (node (ref "CN14") (pin "1") (pinfunction "1_1") (pintype "passive"))
      (node (ref "CN3") (pin "33") (pinfunction "33_33") (pintype "passive"))
    )
    (net (code "84") (name "VDD") (class "Default")
      (node (ref "C10") (pin "2") (pinfunction "2_2") (pintype "passive"))
      (node (ref "C11") (pin "2") (pinfunction "2_2") (pintype "passive"))
      (node (ref "C2") (pin "2") (pinfunction "2_2") (pintype "passive"))
      (node (ref "C3") (pin "2") (pinfunction "2_2") (pintype "passive"))
      (node (ref "C4") (pin "2") (pinfunction "2_2") (pintype "passive"))
      (node (ref "C5") (pin "2") (pinfunction "2_2") (pintype "passive"))
      (node (ref "C6") (pin "2") (pinfunction "2_2") (pintype "passive"))
      (node (ref "C7") (pin "2") (pinfunction "2_2") (pintype "passive"))
      (node (ref "C8") (pin "2") (pinfunction "2_2") (pintype "passive"))
      (node (ref "C9") (pin "2") (pinfunction "2_2") (pintype "passive"))
      (node (ref "CN1") (pin "11") (pinfunction "11_11") (pintype "passive"))
      (node (ref "CN1") (pin "18") (pinfunction "18_18") (pintype "passive"))
      (node (ref "CN1") (pin "2") (pinfunction "2_2") (pintype "passive"))
      (node (ref "CN1") (pin "30") (pinfunction "30_30") (pintype "passive"))
      (node (ref "CN1") (pin "32") (pinfunction "32_32") (pintype "passive"))
      (node (ref "CN1") (pin "48") (pinfunction "48_48") (pintype "passive"))
      (node (ref "CN1") (pin "50") (pinfunction "50_50") (pintype "passive"))
      (node (ref "CN2") (pin "1") (pinfunction "1_1") (pintype "passive"))
      (node (ref "CN2") (pin "17") (pinfunction "17_17") (pintype "passive"))
      (node (ref "CN2") (pin "3") (pinfunction "3_3") (pintype "passive"))
      (node (ref "CN2") (pin "31") (pinfunction "31_31") (pintype "passive"))
      (node (ref "CN2") (pin "33") (pinfunction "33_33") (pintype "passive"))
      (node (ref "CN2") (pin "47") (pinfunction "47_47") (pintype "passive"))
      (node (ref "CN2") (pin "49") (pinfunction "49_49") (pintype "passive"))
      (node (ref "CN3") (pin "5") (pinfunction "5_5") (pintype "passive"))
      (node (ref "SB1") (pin "1") (pinfunction "1_1") (pintype "passive"))
    )
    (net (code "85") (name "VDDA") (class "Default")
      (node (ref "C1") (pin "2") (pinfunction "2_2") (pintype "passive"))
      (node (ref "CN1") (pin "20") (pinfunction "20_20") (pintype "passive"))
      (node (ref "CN11") (pin "1") (pinfunction "1_1") (pintype "passive"))
      (node (ref "CN2") (pin "19") (pinfunction "19_19") (pintype "passive"))
      (node (ref "CN4") (pin "7") (pinfunction "7_7") (pintype "passive"))
      (node (ref "CN6") (pin "8") (pinfunction "8_8") (pintype "passive"))
      (node (ref "SB1") (pin "2") (pinfunction "2_2") (pintype "passive"))
    )
    (net (code "86") (name "VIN") (class "Default")
      (node (ref "CN3") (pin "24") (pinfunction "24_24") (pintype "passive"))
      (node (ref "CN5") (pin "8") (pinfunction "8_8") (pintype "passive"))
    )
    (net (code "87") (name "V_TARGET") (class "Default")
      (node (ref "CN1") (pin "4") (pinfunction "4_4") (pintype "passive"))
      (node (ref "CN3") (pin "12") (pinfunction "12_12") (pintype "passive"))
      (node (ref "CN5") (pin "2") (pinfunction "2_2") (pintype "passive"))
    )
    (net (code "88") (name "unconnected-(CN5-Pad1)") (class "Default")
      (node (ref "CN5") (pin "1") (pinfunction "1_1") (pintype "passive+no_connect"))
    )
  )
)
